# valve_ontrol.net
KiCad netlist of a schematic drawn in Altium Designer
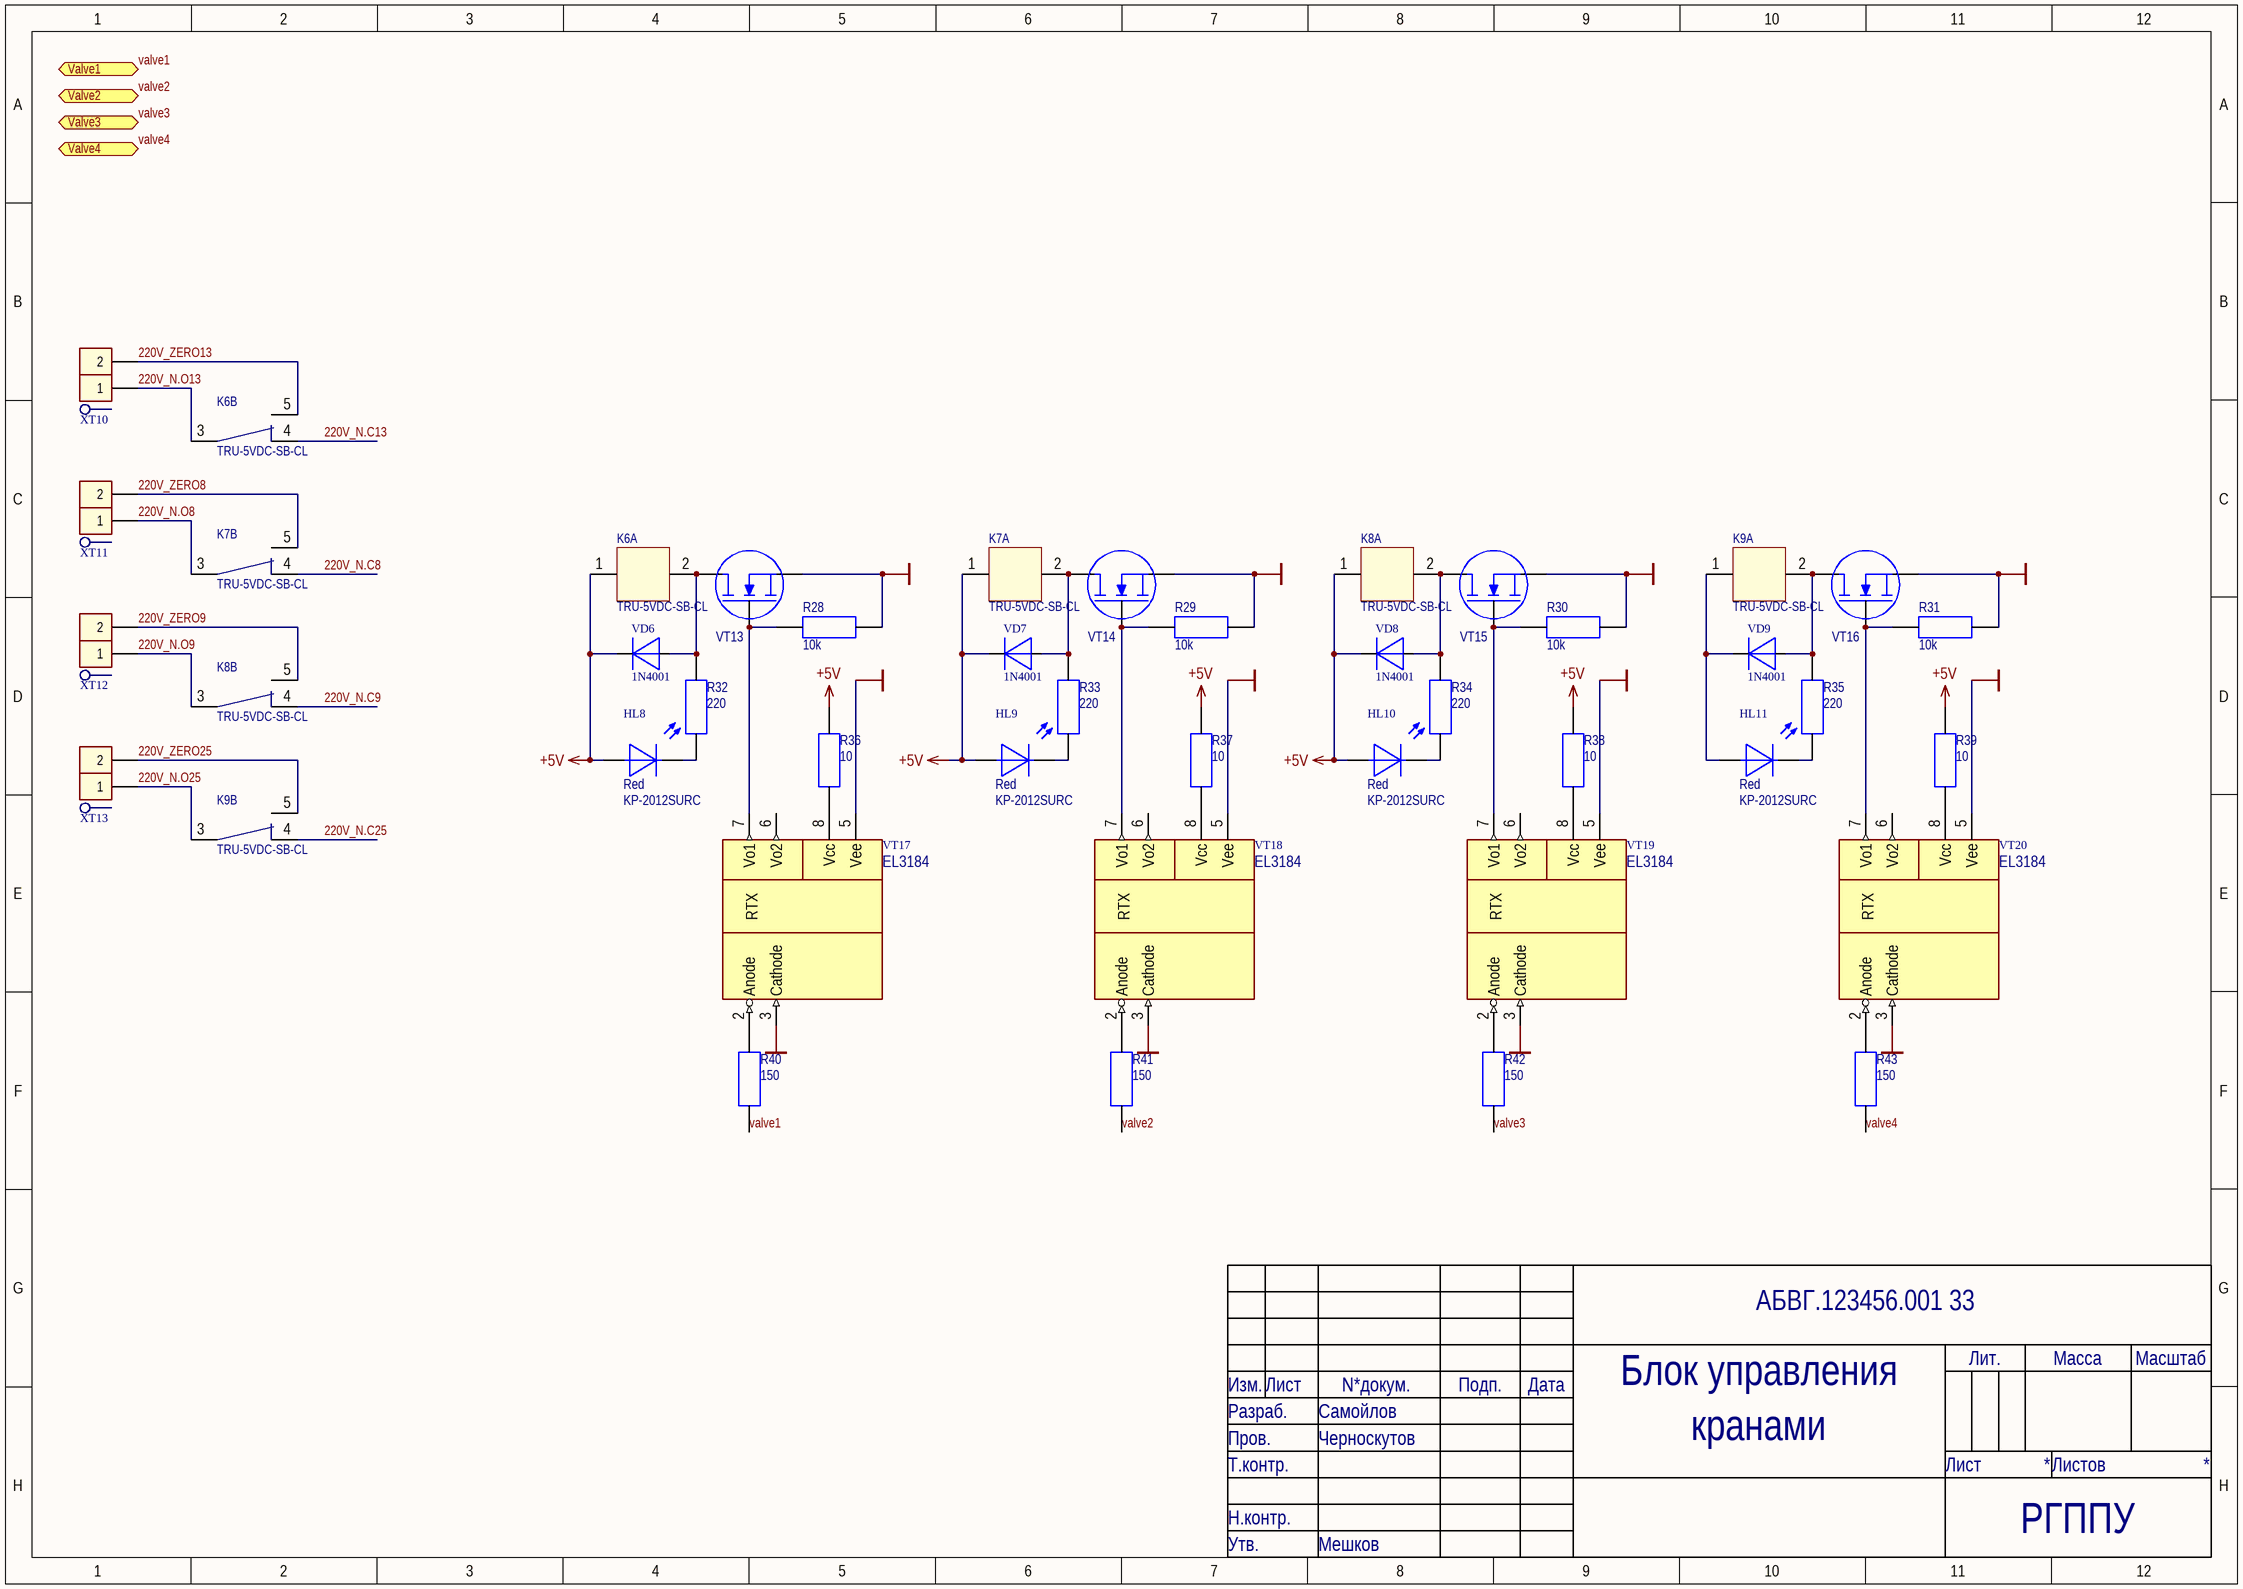
[diagram p0: valveСontrol.SchDoc]

(export (version "E")
  (design (tool "Eeschema 10.0.6"))
  (components
    (comp (ref "HL8")
      (value "Red")
      (footprint "Indicator:DIOMELF2012M")
      (description "Diod LED SMD Red")
      (fields (field (name "MANUFACTURERPARTNUMBER") "KP-2012SURC"))
      (libsource (lib "Indicator") (part "LED1_R"))
    )
    (comp (ref "HL9")
      (value "Red")
      (footprint "Indicator:DIOMELF2012M")
      (description "Diod LED SMD Red")
      (fields (field (name "MANUFACTURERPARTNUMBER") "KP-2012SURC"))
      (libsource (lib "Indicator") (part "LED1_R"))
    )
    (comp (ref "HL10")
      (value "Red")
      (footprint "Indicator:DIOMELF2012M")
      (description "Diod LED SMD Red")
      (fields (field (name "MANUFACTURERPARTNUMBER") "KP-2012SURC"))
      (libsource (lib "Indicator") (part "LED1_R"))
    )
    (comp (ref "HL11")
      (value "Red")
      (footprint "Indicator:DIOMELF2012M")
      (description "Diod LED SMD Red")
      (fields (field (name "MANUFACTURERPARTNUMBER") "KP-2012SURC"))
      (libsource (lib "Indicator") (part "LED1_R"))
    )
    (comp (ref "K6")
      (value "TRU-5VDC-SB-CL")
      (footprint "Switch:TRU-5VDC-SB-CL")
      (libsource (lib "") (part "TRU-5VDC-SB-CL_1"))
    )
    (comp (ref "K7")
      (value "TRU-5VDC-SB-CL")
      (footprint "Switch:TRU-5VDC-SB-CL")
      (libsource (lib "") (part "TRU-5VDC-SB-CL_1"))
    )
    (comp (ref "K8")
      (value "TRU-5VDC-SB-CL")
      (footprint "Switch:TRU-5VDC-SB-CL")
      (libsource (lib "Switch") (part "TRU-5VDC-SB-CL"))
    )
    (comp (ref "K9")
      (value "TRU-5VDC-SB-CL")
      (footprint "Switch:TRU-5VDC-SB-CL")
      (libsource (lib "Switch") (part "TRU-5VDC-SB-CL"))
    )
    (comp (ref "R28")
      (value "10k")
      (footprint "SMDRC0805")
      (description "Generic resistor")
      (fields (field (name "PARTNUMBER") "Resistor 0805 10k"))
      (libsource (lib "") (part "Resistor_2"))
    )
    (comp (ref "R29")
      (value "10k")
      (footprint "SMDRC0805")
      (description "Generic resistor")
      (fields (field (name "PARTNUMBER") "Resistor 0805 10k"))
      (libsource (lib "") (part "Resistor_2"))
    )
    (comp (ref "R30")
      (value "10k")
      (footprint "SMDRC0805")
      (description "Generic resistor")
      (fields (field (name "PARTNUMBER") "Resistor 0805 10k"))
      (libsource (lib "") (part "Resistor_2"))
    )
    (comp (ref "R31")
      (value "10k")
      (footprint "SMDRC0805")
      (description "Generic resistor")
      (fields (field (name "PARTNUMBER") "Resistor 0805 10k"))
      (libsource (lib "") (part "Resistor_2"))
    )
    (comp (ref "R32")
      (value "220")
      (footprint "SMDRC0805")
      (description "Generic resistor")
      (fields (field (name "PARTNUMBER") "Resistor 0805 220"))
      (libsource (lib "") (part "Resistor_1"))
    )
    (comp (ref "R33")
      (value "220")
      (footprint "SMDRC0805")
      (description "Generic resistor")
      (fields (field (name "PARTNUMBER") "Resistor 0805 220"))
      (libsource (lib "") (part "Resistor_1"))
    )
    (comp (ref "R34")
      (value "220")
      (footprint "SMDRC0805")
      (description "Generic resistor")
      (fields (field (name "PARTNUMBER") "Resistor 0805 220"))
      (libsource (lib "") (part "Resistor_1"))
    )
    (comp (ref "R35")
      (value "220")
      (footprint "SMDRC0805")
      (description "Generic resistor")
      (fields (field (name "PARTNUMBER") "Resistor 0805 220"))
      (libsource (lib "") (part "Resistor_1"))
    )
    (comp (ref "R36")
      (value "10")
      (footprint "SMDRC0805")
      (description "Generic resistor")
      (fields (field (name "PARTNUMBER") "Resistor 0805 10"))
      (libsource (lib "library") (part "Resistor"))
    )
    (comp (ref "R37")
      (value "10")
      (footprint "SMDRC0805")
      (description "Generic resistor")
      (fields (field (name "PARTNUMBER") "Resistor 0805 10"))
      (libsource (lib "library") (part "Resistor"))
    )
    (comp (ref "R38")
      (value "10")
      (footprint "SMDRC0805")
      (description "Generic resistor")
      (fields (field (name "PARTNUMBER") "Resistor 0805 10"))
      (libsource (lib "library") (part "Resistor"))
    )
    (comp (ref "R39")
      (value "10")
      (footprint "SMDRC0805")
      (description "Generic resistor")
      (fields (field (name "PARTNUMBER") "Resistor 0805 10"))
      (libsource (lib "library") (part "Resistor"))
    )
    (comp (ref "R40")
      (value "150")
      (footprint "SMDRC0805")
      (description "Generic resistor")
      (fields (field (name "PARTNUMBER") "Resistor 0805 150"))
      (libsource (lib "library") (part "Resistor"))
    )
    (comp (ref "R41")
      (value "150")
      (footprint "SMDRC0805")
      (description "Generic resistor")
      (fields (field (name "PARTNUMBER") "Resistor 0805 150"))
      (libsource (lib "library") (part "Resistor"))
    )
    (comp (ref "R42")
      (value "150")
      (footprint "SMDRC0805")
      (description "Generic resistor")
      (fields (field (name "PARTNUMBER") "Resistor 0805 150"))
      (libsource (lib "library") (part "Resistor"))
    )
    (comp (ref "R43")
      (value "150")
      (footprint "SMDRC0805")
      (description "Generic resistor")
      (fields (field (name "PARTNUMBER") "Resistor 0805 150"))
      (libsource (lib "library") (part "Resistor"))
    )
    (comp (ref "VD6")
      (value "1N4001")
      (footprint "DIod:PinDiode")
      (description "Rectifying diode")
      (fields (field (name "MANUFACTURERPARTNUMBER") "1N4001"))
      (libsource (lib "Diod") (part "1N4001"))
    )
    (comp (ref "VD7")
      (value "1N4001")
      (footprint "DIod:PinDiode")
      (description "Rectifying diode")
      (fields (field (name "MANUFACTURERPARTNUMBER") "1N4001"))
      (libsource (lib "Diod") (part "1N4001"))
    )
    (comp (ref "VD8")
      (value "1N4001")
      (footprint "DIod:PinDiode")
      (description "Rectifying diode")
      (fields (field (name "MANUFACTURERPARTNUMBER") "1N4001"))
      (libsource (lib "Diod") (part "1N4001"))
    )
    (comp (ref "VD9")
      (value "1N4001")
      (footprint "DIod:PinDiode")
      (description "Rectifying diode")
      (fields (field (name "MANUFACTURERPARTNUMBER") "1N4001"))
      (libsource (lib "Diod") (part "1N4001"))
    )
    (comp (ref "VT13")
      (value "2N7002")
      (footprint "Standard:SOT23 (TO-236AB)")
      (description "60V, 300mA N-channel Trench MOSFET")
      (libsource (lib "Transistor") (part "2N7002 n-MOSFET"))
    )
    (comp (ref "VT14")
      (value "2N7002")
      (footprint "Standard:SOT23 (TO-236AB)")
      (description "60V, 300mA N-channel Trench MOSFET")
      (libsource (lib "Transistor") (part "2N7002 n-MOSFET"))
    )
    (comp (ref "VT15")
      (value "2N7002")
      (footprint "Standard:SOT23 (TO-236AB)")
      (description "60V, 300mA N-channel Trench MOSFET")
      (libsource (lib "Transistor") (part "2N7002 n-MOSFET"))
    )
    (comp (ref "VT16")
      (value "2N7002")
      (footprint "Standard:SOT23 (TO-236AB)")
      (description "60V, 300mA N-channel Trench MOSFET")
      (libsource (lib "Transistor") (part "2N7002 n-MOSFET"))
    )
    (comp (ref "VT17")
      (value "EL3184")
      (footprint "DIP8")
      (description "Optocouple IGBT driver")
      (fields
        (field (name "MANUFACTURER") "Everlight Electronics Co. Ltd")
        (field (name "MANUFACTURERPARTNUMBER") "EL3184")
      )
      (libsource (lib "Interface") (part "EL3184"))
    )
    (comp (ref "VT18")
      (value "EL3184")
      (footprint "DIP8")
      (description "Optocouple IGBT driver")
      (fields
        (field (name "MANUFACTURER") "Everlight Electronics Co. Ltd")
        (field (name "MANUFACTURERPARTNUMBER") "EL3184")
      )
      (libsource (lib "Interface") (part "EL3184"))
    )
    (comp (ref "VT19")
      (value "EL3184")
      (footprint "DIP8")
      (description "Optocouple IGBT driver")
      (fields
        (field (name "MANUFACTURER") "Everlight Electronics Co. Ltd")
        (field (name "MANUFACTURERPARTNUMBER") "EL3184")
      )
      (libsource (lib "Interface") (part "EL3184"))
    )
    (comp (ref "VT20")
      (value "EL3184")
      (footprint "DIP8")
      (description "Optocouple IGBT driver")
      (fields
        (field (name "MANUFACTURER") "Everlight Electronics Co. Ltd")
        (field (name "MANUFACTURERPARTNUMBER") "EL3184")
      )
      (libsource (lib "Interface") (part "EL3184"))
    )
    (comp (ref "XT10")
      (value "305-021-12")
      (footprint "330-021-12")
      (description "Demountable connection  2-pin")
      (fields (field (name "MANUFACTURER") "Degson Electronics Co., Ltd"))
      (libsource (lib "Connector") (part "Con2_D 330-021-12"))
    )
    (comp (ref "XT11")
      (value "305-021-12")
      (footprint "330-021-12")
      (description "Demountable connection  2-pin")
      (fields (field (name "MANUFACTURER") "Degson Electronics Co., Ltd"))
      (libsource (lib "Connector") (part "Con2_D 330-021-12"))
    )
    (comp (ref "XT12")
      (value "305-021-12")
      (footprint "330-021-12")
      (description "Demountable connection  2-pin")
      (fields (field (name "MANUFACTURER") "Degson Electronics Co., Ltd"))
      (libsource (lib "Connector") (part "Con2_D 330-021-12"))
    )
    (comp (ref "XT13")
      (value "305-021-12")
      (footprint "330-021-12")
      (description "Demountable connection  2-pin")
      (fields (field (name "MANUFACTURER") "Degson Electronics Co., Ltd"))
      (libsource (lib "Connector") (part "Con2_D 330-021-12"))
    )
  )
  (nets
    (net (code "1") (name "+5V") (class "Default")
      (node (ref "HL10") (pin "1") (pinfunction "1_1") (pintype "passive"))
      (node (ref "HL8") (pin "1") (pinfunction "1_1") (pintype "passive"))
      (node (ref "HL9") (pin "1") (pinfunction "1_1") (pintype "passive"))
      (node (ref "K6") (pin "1") (pinfunction "1_1") (pintype "passive"))
      (node (ref "K7") (pin "1") (pinfunction "1_1") (pintype "passive"))
      (node (ref "K8") (pin "1") (pinfunction "1_1") (pintype "passive"))
      (node (ref "R36") (pin "2") (pinfunction "2_2") (pintype "passive"))
      (node (ref "R37") (pin "2") (pinfunction "2_2") (pintype "passive"))
      (node (ref "R38") (pin "2") (pinfunction "2_2") (pintype "passive"))
      (node (ref "R39") (pin "2") (pinfunction "2_2") (pintype "passive"))
      (node (ref "VD6") (pin "K") (pinfunction "K_K") (pintype "passive"))
      (node (ref "VD7") (pin "K") (pinfunction "K_K") (pintype "passive"))
      (node (ref "VD8") (pin "K") (pinfunction "K_K") (pintype "passive"))
    )
    (net (code "2") (name "/220V_N.C8") (class "Default")
      (node (ref "K7") (pin "4") (pinfunction "4_4") (pintype "passive"))
    )
    (net (code "3") (name "/220V_N.C9") (class "Default")
      (node (ref "K8") (pin "4") (pinfunction "4_4") (pintype "passive"))
    )
    (net (code "4") (name "/220V_N.C13") (class "Default")
      (node (ref "K6") (pin "4") (pinfunction "4_4") (pintype "passive"))
    )
    (net (code "5") (name "/220V_N.C25") (class "Default")
      (node (ref "K9") (pin "4") (pinfunction "4_4") (pintype "passive"))
    )
    (net (code "6") (name "/220V_N.O8") (class "Default")
      (node (ref "K7") (pin "3") (pinfunction "3_3") (pintype "passive"))
      (node (ref "XT11") (pin "1") (pinfunction "1_1") (pintype "passive"))
    )
    (net (code "7") (name "/220V_N.O9") (class "Default")
      (node (ref "K8") (pin "3") (pinfunction "3_3") (pintype "passive"))
      (node (ref "XT12") (pin "1") (pinfunction "1_1") (pintype "passive"))
    )
    (net (code "8") (name "/220V_N.O13") (class "Default")
      (node (ref "K6") (pin "3") (pinfunction "3_3") (pintype "passive"))
      (node (ref "XT10") (pin "1") (pinfunction "1_1") (pintype "passive"))
    )
    (net (code "9") (name "/220V_N.O25") (class "Default")
      (node (ref "K9") (pin "3") (pinfunction "3_3") (pintype "passive"))
      (node (ref "XT13") (pin "1") (pinfunction "1_1") (pintype "passive"))
    )
    (net (code "10") (name "/220V_ZERO8") (class "Default")
      (node (ref "K7") (pin "5") (pinfunction "5_5") (pintype "passive"))
      (node (ref "XT11") (pin "2") (pinfunction "2_2") (pintype "passive"))
    )
    (net (code "11") (name "/220V_ZERO9") (class "Default")
      (node (ref "K8") (pin "5") (pinfunction "5_5") (pintype "passive"))
      (node (ref "XT12") (pin "2") (pinfunction "2_2") (pintype "passive"))
    )
    (net (code "12") (name "/220V_ZERO13") (class "Default")
      (node (ref "K6") (pin "5") (pinfunction "5_5") (pintype "passive"))
      (node (ref "XT10") (pin "2") (pinfunction "2_2") (pintype "passive"))
    )
    (net (code "13") (name "/220V_ZERO25") (class "Default")
      (node (ref "K9") (pin "5") (pinfunction "5_5") (pintype "passive"))
      (node (ref "XT13") (pin "2") (pinfunction "2_2") (pintype "passive"))
    )
    (net (code "14") (name "/valve1") (class "Default")
      (node (ref "R40") (pin "1") (pinfunction "1_1") (pintype "passive"))
    )
    (net (code "15") (name "/valve2") (class "Default")
      (node (ref "R41") (pin "1") (pinfunction "1_1") (pintype "passive"))
    )
    (net (code "16") (name "/valve3") (class "Default")
      (node (ref "R42") (pin "1") (pinfunction "1_1") (pintype "passive"))
    )
    (net (code "17") (name "/valve4") (class "Default")
      (node (ref "R43") (pin "1") (pinfunction "1_1") (pintype "passive"))
    )
    (net (code "18") (name "GND") (class "Default")
      (node (ref "R28") (pin "2") (pinfunction "2_2") (pintype "passive"))
      (node (ref "R29") (pin "2") (pinfunction "2_2") (pintype "passive"))
      (node (ref "R30") (pin "2") (pinfunction "2_2") (pintype "passive"))
      (node (ref "R31") (pin "2") (pinfunction "2_2") (pintype "passive"))
      (node (ref "VT13") (pin "2") (pinfunction "S_2") (pintype "passive"))
      (node (ref "VT14") (pin "2") (pinfunction "S_2") (pintype "passive"))
      (node (ref "VT15") (pin "2") (pinfunction "S_2") (pintype "passive"))
      (node (ref "VT16") (pin "2") (pinfunction "S_2") (pintype "passive"))
      (node (ref "VT17") (pin "3") (pinfunction "Cathode_3") (pintype "input"))
      (node (ref "VT17") (pin "5") (pinfunction "Vee_5") (pintype "power_in"))
      (node (ref "VT18") (pin "3") (pinfunction "Cathode_3") (pintype "input"))
      (node (ref "VT18") (pin "5") (pinfunction "Vee_5") (pintype "power_in"))
      (node (ref "VT19") (pin "3") (pinfunction "Cathode_3") (pintype "input"))
      (node (ref "VT19") (pin "5") (pinfunction "Vee_5") (pintype "power_in"))
      (node (ref "VT20") (pin "3") (pinfunction "Cathode_3") (pintype "input"))
      (node (ref "VT20") (pin "5") (pinfunction "Vee_5") (pintype "power_in"))
    )
    (net (code "19") (name "Net-(HL8-Pad2)") (class "Default")
      (node (ref "HL8") (pin "2") (pinfunction "2_2") (pintype "passive"))
      (node (ref "R32") (pin "2") (pinfunction "2_2") (pintype "passive"))
    )
    (net (code "20") (name "Net-(HL9-Pad2)") (class "Default")
      (node (ref "HL9") (pin "2") (pinfunction "2_2") (pintype "passive"))
      (node (ref "R33") (pin "2") (pinfunction "2_2") (pintype "passive"))
    )
    (net (code "21") (name "Net-(HL10-Pad2)") (class "Default")
      (node (ref "HL10") (pin "2") (pinfunction "2_2") (pintype "passive"))
      (node (ref "R34") (pin "2") (pinfunction "2_2") (pintype "passive"))
    )
    (net (code "22") (name "Net-(HL11-Pad1)") (class "Default")
      (node (ref "HL11") (pin "1") (pinfunction "1_1") (pintype "passive"))
      (node (ref "K9") (pin "1") (pinfunction "1_1") (pintype "passive"))
      (node (ref "VD9") (pin "K") (pinfunction "K_K") (pintype "passive"))
    )
    (net (code "23") (name "Net-(HL11-Pad2)") (class "Default")
      (node (ref "HL11") (pin "2") (pinfunction "2_2") (pintype "passive"))
      (node (ref "R35") (pin "2") (pinfunction "2_2") (pintype "passive"))
    )
    (net (code "24") (name "Net-(VT13-D)") (class "Default")
      (node (ref "K6") (pin "2") (pinfunction "2_2") (pintype "passive"))
      (node (ref "R32") (pin "1") (pinfunction "1_1") (pintype "passive"))
      (node (ref "VD6") (pin "A") (pinfunction "A_A") (pintype "passive"))
      (node (ref "VT13") (pin "3") (pinfunction "D_3") (pintype "passive"))
    )
    (net (code "25") (name "Net-(VT13-G)") (class "Default")
      (node (ref "R28") (pin "1") (pinfunction "1_1") (pintype "passive"))
      (node (ref "VT13") (pin "1") (pinfunction "G_1") (pintype "passive"))
      (node (ref "VT17") (pin "7") (pinfunction "Vo1_7") (pintype "output"))
    )
    (net (code "26") (name "Net-(VT14-D)") (class "Default")
      (node (ref "K7") (pin "2") (pinfunction "2_2") (pintype "passive"))
      (node (ref "R33") (pin "1") (pinfunction "1_1") (pintype "passive"))
      (node (ref "VD7") (pin "A") (pinfunction "A_A") (pintype "passive"))
      (node (ref "VT14") (pin "3") (pinfunction "D_3") (pintype "passive"))
    )
    (net (code "27") (name "Net-(VT14-G)") (class "Default")
      (node (ref "R29") (pin "1") (pinfunction "1_1") (pintype "passive"))
      (node (ref "VT14") (pin "1") (pinfunction "G_1") (pintype "passive"))
      (node (ref "VT18") (pin "7") (pinfunction "Vo1_7") (pintype "output"))
    )
    (net (code "28") (name "Net-(VT15-D)") (class "Default")
      (node (ref "K8") (pin "2") (pinfunction "2_2") (pintype "passive"))
      (node (ref "R34") (pin "1") (pinfunction "1_1") (pintype "passive"))
      (node (ref "VD8") (pin "A") (pinfunction "A_A") (pintype "passive"))
      (node (ref "VT15") (pin "3") (pinfunction "D_3") (pintype "passive"))
    )
    (net (code "29") (name "Net-(VT15-G)") (class "Default")
      (node (ref "R30") (pin "1") (pinfunction "1_1") (pintype "passive"))
      (node (ref "VT15") (pin "1") (pinfunction "G_1") (pintype "passive"))
      (node (ref "VT19") (pin "7") (pinfunction "Vo1_7") (pintype "output"))
    )
    (net (code "30") (name "Net-(VT16-D)") (class "Default")
      (node (ref "K9") (pin "2") (pinfunction "2_2") (pintype "passive"))
      (node (ref "R35") (pin "1") (pinfunction "1_1") (pintype "passive"))
      (node (ref "VD9") (pin "A") (pinfunction "A_A") (pintype "passive"))
      (node (ref "VT16") (pin "3") (pinfunction "D_3") (pintype "passive"))
    )
    (net (code "31") (name "Net-(VT16-G)") (class "Default")
      (node (ref "R31") (pin "1") (pinfunction "1_1") (pintype "passive"))
      (node (ref "VT16") (pin "1") (pinfunction "G_1") (pintype "passive"))
      (node (ref "VT20") (pin "7") (pinfunction "Vo1_7") (pintype "output"))
    )
    (net (code "32") (name "Net-(VT17-Anode)") (class "Default")
      (node (ref "R40") (pin "2") (pinfunction "2_2") (pintype "passive"))
      (node (ref "VT17") (pin "2") (pinfunction "Anode_2") (pintype "input"))
    )
    (net (code "33") (name "Net-(VT17-Vcc)") (class "Default")
      (node (ref "R36") (pin "1") (pinfunction "1_1") (pintype "passive"))
      (node (ref "VT17") (pin "8") (pinfunction "Vcc_8") (pintype "power_in"))
    )
    (net (code "34") (name "Net-(VT18-Anode)") (class "Default")
      (node (ref "R41") (pin "2") (pinfunction "2_2") (pintype "passive"))
      (node (ref "VT18") (pin "2") (pinfunction "Anode_2") (pintype "input"))
    )
    (net (code "35") (name "Net-(VT18-Vcc)") (class "Default")
      (node (ref "R37") (pin "1") (pinfunction "1_1") (pintype "passive"))
      (node (ref "VT18") (pin "8") (pinfunction "Vcc_8") (pintype "power_in"))
    )
    (net (code "36") (name "Net-(VT19-Anode)") (class "Default")
      (node (ref "R42") (pin "2") (pinfunction "2_2") (pintype "passive"))
      (node (ref "VT19") (pin "2") (pinfunction "Anode_2") (pintype "input"))
    )
    (net (code "37") (name "Net-(VT19-Vcc)") (class "Default")
      (node (ref "R38") (pin "1") (pinfunction "1_1") (pintype "passive"))
      (node (ref "VT19") (pin "8") (pinfunction "Vcc_8") (pintype "power_in"))
    )
    (net (code "38") (name "Net-(VT20-Anode)") (class "Default")
      (node (ref "R43") (pin "2") (pinfunction "2_2") (pintype "passive"))
      (node (ref "VT20") (pin "2") (pinfunction "Anode_2") (pintype "input"))
    )
    (net (code "39") (name "Net-(VT20-Vcc)") (class "Default")
      (node (ref "R39") (pin "1") (pinfunction "1_1") (pintype "passive"))
      (node (ref "VT20") (pin "8") (pinfunction "Vcc_8") (pintype "power_in"))
    )
    (net (code "40") (name "unconnected-(VT17-Vo2-Pad6)") (class "Default")
      (node (ref "VT17") (pin "6") (pinfunction "Vo2_6") (pintype "output"))
    )
    (net (code "41") (name "unconnected-(VT18-Vo2-Pad6)") (class "Default")
      (node (ref "VT18") (pin "6") (pinfunction "Vo2_6") (pintype "output"))
    )
    (net (code "42") (name "unconnected-(VT19-Vo2-Pad6)") (class "Default")
      (node (ref "VT19") (pin "6") (pinfunction "Vo2_6") (pintype "output"))
    )
    (net (code "43") (name "unconnected-(VT20-Vo2-Pad6)") (class "Default")
      (node (ref "VT20") (pin "6") (pinfunction "Vo2_6") (pintype "output"))
    )
  )
)
